# BSPDSpring24.net
KiCad netlist of a schematic drawn in Altium Designer
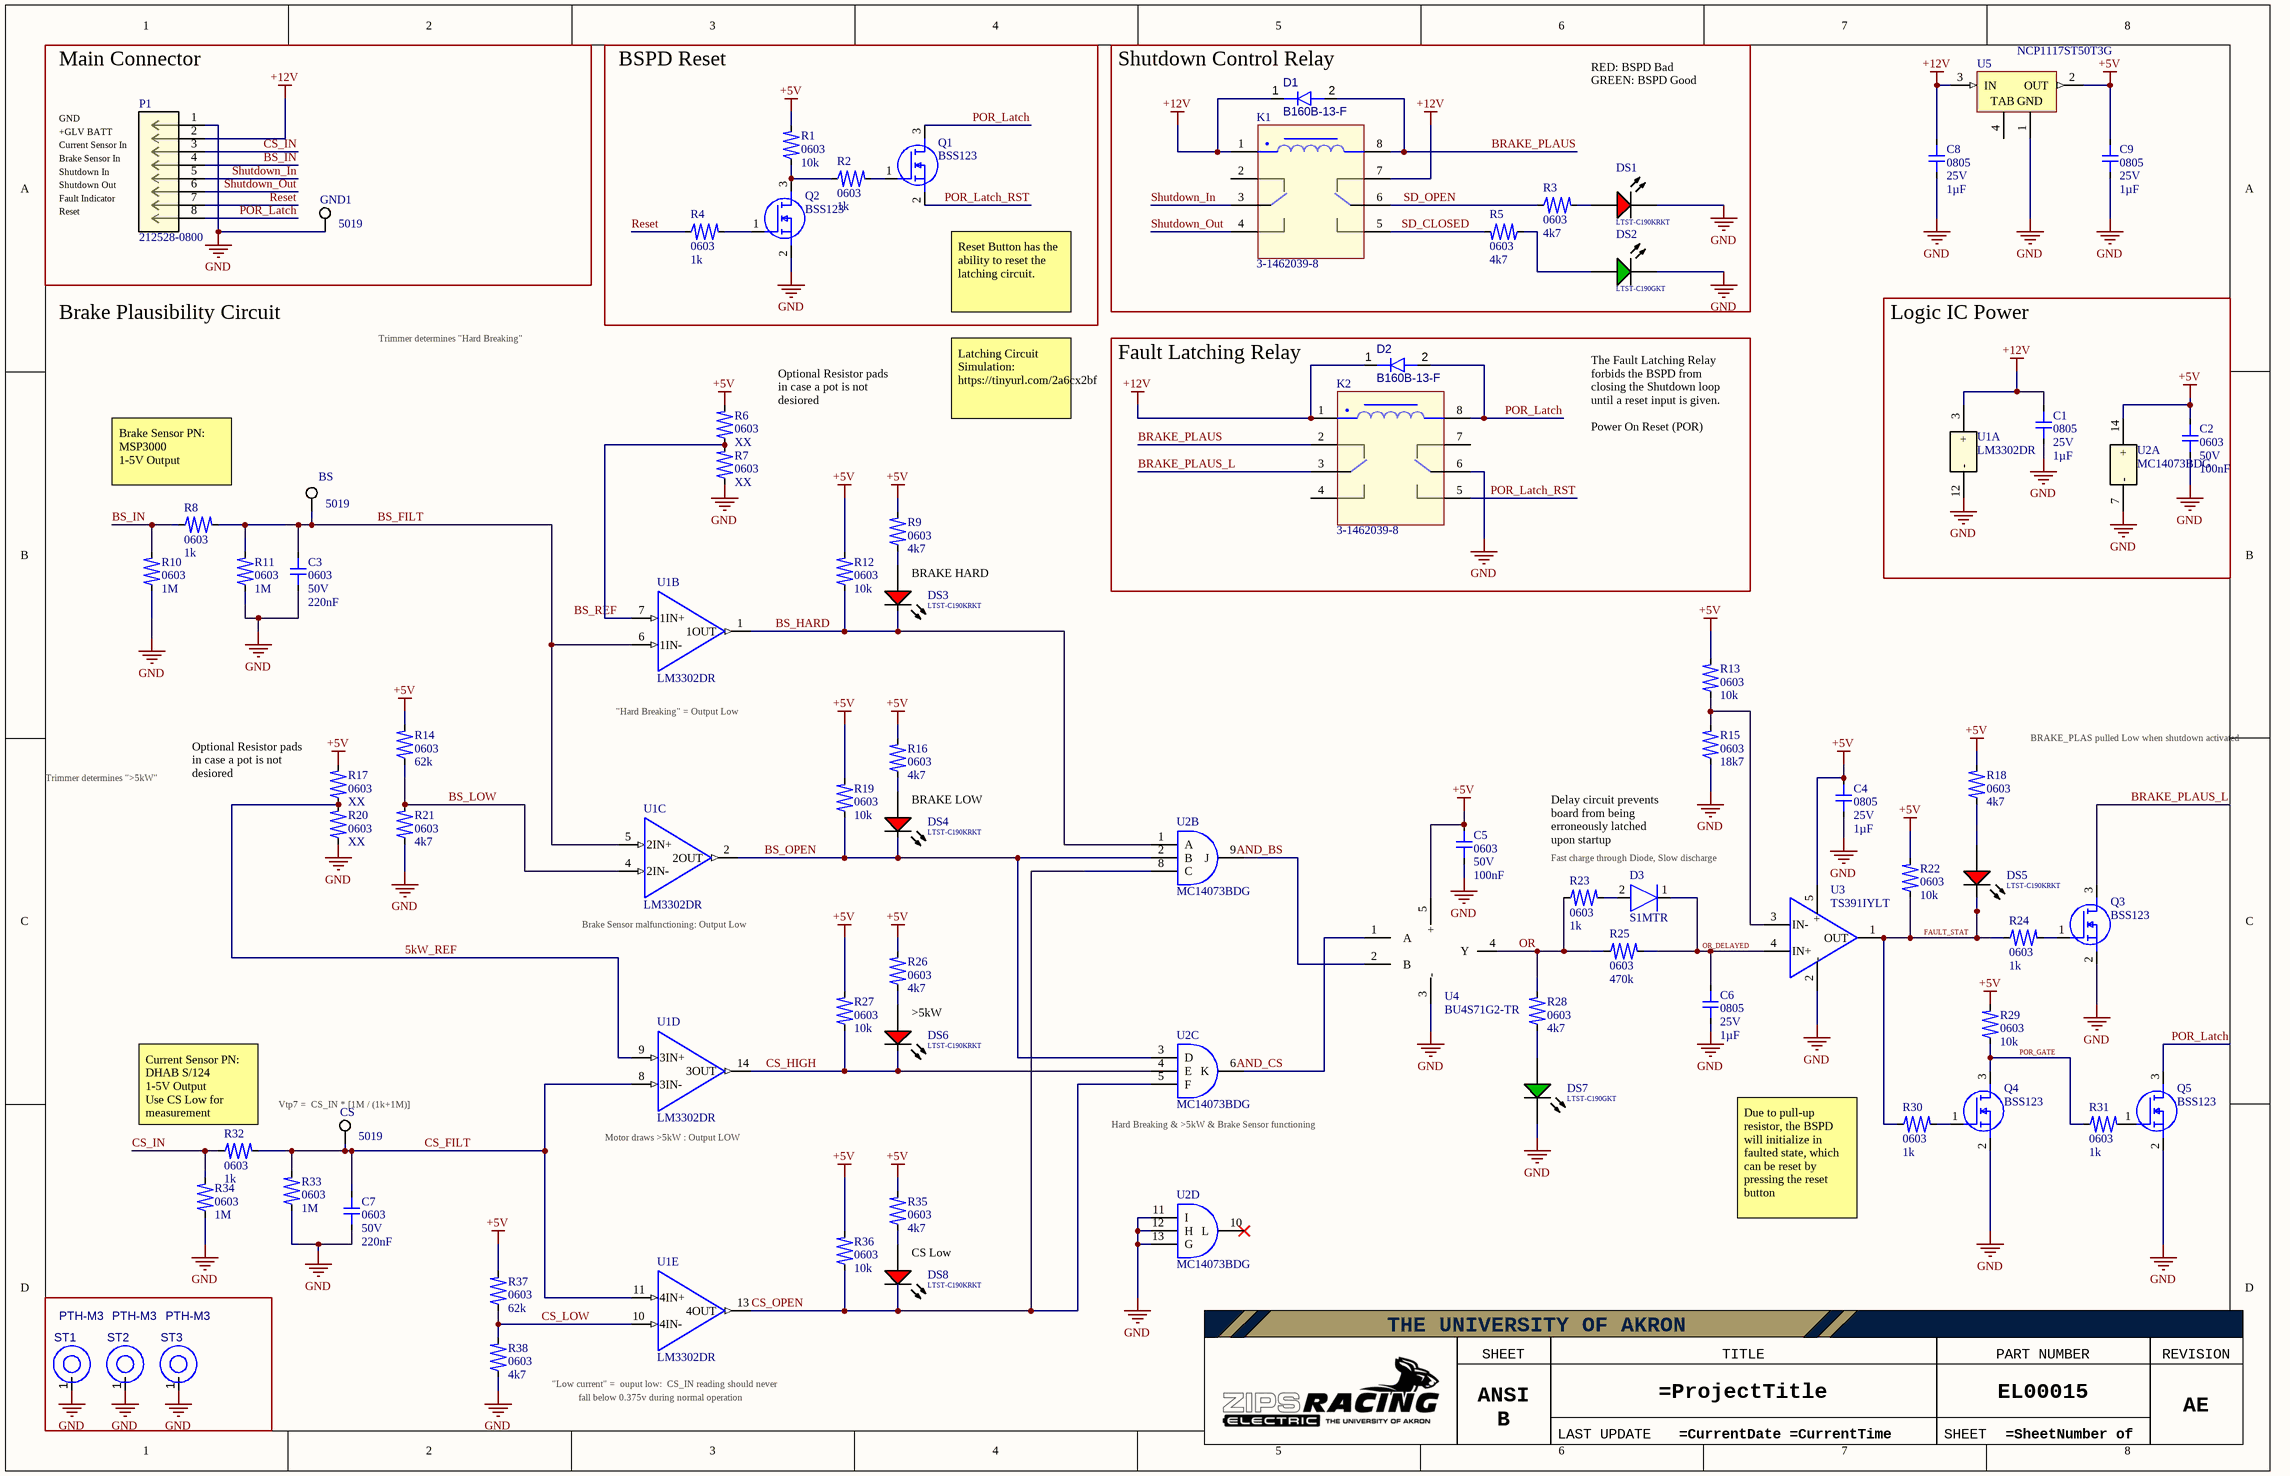
[diagram p0: BSPDSpring24.SchDoc]

(export (version "E")
  (design (tool "Eeschema 10.0.6"))
  (components
    (comp (ref "BS")
      (value "5019")
      (footprint "KSTN-5019_V")
      (description "Interconnection Device")
      (libsource (lib "Zips Racing Electric") (part "TESTPOINT_WHITE"))
    )
    (comp (ref "C1")
      (value "1µF")
      (footprint "0805")
      (description "Capacitor, 0805")
      (fields (field (name "VOLTAGE") "25V") (field (name "Comment") "Capacitor 1uF 0805 25V"))
      (libsource (lib "Zips Racing Electric") (part "CAP-0603"))
    )
    (comp (ref "C2")
      (value "100nF")
      (footprint "0603")
      (description "Capacitor, 0603, 5%")
      (fields (field (name "VOLTAGE") "50V") (field (name "Comment") "Capacitor 100nF 0603 5%"))
      (libsource (lib "Zips Racing Electric") (part "CAP-0603"))
    )
    (comp (ref "C3")
      (value "220nF")
      (footprint "0603")
      (description "Capacitor, 0603, 5%")
      (fields (field (name "VOLTAGE") "50V") (field (name "Comment") "Capacitor 220nF 0603 5%"))
      (libsource (lib "Zips Racing Electric") (part "CAP-0603"))
    )
    (comp (ref "C4")
      (value "1µF")
      (footprint "0805")
      (description "Capacitor, 0805")
      (fields (field (name "VOLTAGE") "25V") (field (name "Comment") "Capacitor 1uF 0805 25V"))
      (libsource (lib "Zips Racing Electric") (part "CAP-0603"))
    )
    (comp (ref "C5")
      (value "100nF")
      (footprint "0603")
      (description "Capacitor, 0603, 5%")
      (fields (field (name "VOLTAGE") "50V") (field (name "Comment") "Capacitor 100nF 0603 5%"))
      (libsource (lib "Zips Racing Electric") (part "CAP-0603"))
    )
    (comp (ref "C6")
      (value "1µF")
      (footprint "0805")
      (description "Capacitor, 0805")
      (fields (field (name "VOLTAGE") "25V") (field (name "Comment") "Capacitor 1uF 0805 25V"))
      (libsource (lib "Zips Racing Electric") (part "CAP-0603"))
    )
    (comp (ref "C7")
      (value "220nF")
      (footprint "0603")
      (description "Capacitor, 0603, 5%")
      (fields (field (name "VOLTAGE") "50V") (field (name "Comment") "Capacitor 220nF 0603 5%"))
      (libsource (lib "Zips Racing Electric") (part "CAP-0603"))
    )
    (comp (ref "C8")
      (value "1µF")
      (footprint "0805")
      (description "Capacitor, 0805")
      (fields (field (name "VOLTAGE") "25V") (field (name "Comment") "Capacitor 1uF 0805 25V"))
      (libsource (lib "Zips Racing Electric") (part "CAP-0603"))
    )
    (comp (ref "C9")
      (value "1µF")
      (footprint "0805")
      (description "Capacitor, 0805")
      (fields (field (name "VOLTAGE") "25V") (field (name "Comment") "Capacitor 1uF 0805 25V"))
      (libsource (lib "Zips Racing Electric") (part "CAP-0603"))
    )
    (comp (ref "CS")
      (value "5019")
      (footprint "KSTN-5019_V")
      (description "Interconnection Device")
      (libsource (lib "Zips Racing Electric") (part "TESTPOINT_WHITE"))
    )
    (comp (ref "D1")
      (value "B160B-13-F")
      (footprint "FP-SMB-MFG")
      (description "Rectifier Diode, Schottky, 1 Phase, 1 Element, 1A, 60V V(RRM), Silicon")
      (libsource (lib "Zips Racing Electric") (part "DIODE-2"))
    )
    (comp (ref "D2")
      (value "B160B-13-F")
      (footprint "FP-SMB-MFG")
      (description "Rectifier Diode, Schottky, 1 Phase, 1 Element, 1A, 60V V(RRM), Silicon")
      (libsource (lib "Zips Racing Electric") (part "DIODE-2"))
    )
    (comp (ref "D3")
      (value "S1MTR")
      (footprint "SMA_SDS")
      (description "Diode Standard 1000 V 1A Surface Mount SMA (DO-214AC)")
      (fields
        (field (name "COPYRIGHT") "Copyright (C) 2021 Ultra Librarian. All rights reserved.")
        (field (name "SOURCE") "Zips_Racing_Electric.SchLib")
      )
      (libsource (lib "Zips Racing Electric") (part "B160B-13-F"))
    )
    (comp (ref "DS1")
      (value "LTST-C190KRKT")
      (footprint "LTST-C191KRKT_V")
      (description "LED Uni-Color Red, 62.5 mW, 25 mA, -30 to 85 degC, 2-Pin SMD, RoHS, Tape and Reel")
      (fields (field (name "POWER") "75mW") (field (name "MANUFACTURER") "Lite-On"))
      (libsource (lib "Zips Racing Electric") (part "LED-RED-AK-2"))
    )
    (comp (ref "DS2")
      (value "LTST-C190GKT")
      (footprint "LTST-C190GKT_V")
      (description "LED Uni-Color Green, 100 mW, 30 mA, -55 to 85 degC, 2-Pin SMD, RoHS, Tape and Reel")
      (fields (field (name "POWER") "100mW") (field (name "MANUFACTURER") "Lite-On"))
      (libsource (lib "Zips Racing Electric") (part "LED-GREEN-AK-2"))
    )
    (comp (ref "DS3")
      (value "LTST-C190KRKT")
      (footprint "LTST-C191KRKT_V")
      (description "LED Uni-Color Red, 62.5 mW, 25 mA, -30 to 85 degC, 2-Pin SMD, RoHS, Tape and Reel")
      (fields (field (name "POWER") "75mW") (field (name "MANUFACTURER") "Lite-On"))
      (libsource (lib "Zips Racing Electric") (part "LED-RED-AK-2"))
    )
    (comp (ref "DS4")
      (value "LTST-C190KRKT")
      (footprint "LTST-C191KRKT_V")
      (description "LED Uni-Color Red, 62.5 mW, 25 mA, -30 to 85 degC, 2-Pin SMD, RoHS, Tape and Reel")
      (fields (field (name "POWER") "75mW") (field (name "MANUFACTURER") "Lite-On"))
      (libsource (lib "Zips Racing Electric") (part "LED-RED-AK-2"))
    )
    (comp (ref "DS5")
      (value "LTST-C190KRKT")
      (footprint "LTST-C191KRKT_V")
      (description "LED Uni-Color Red, 62.5 mW, 25 mA, -30 to 85 degC, 2-Pin SMD, RoHS, Tape and Reel")
      (fields (field (name "POWER") "75mW") (field (name "MANUFACTURER") "Lite-On"))
      (libsource (lib "Zips Racing Electric") (part "LED-RED-AK-2"))
    )
    (comp (ref "DS6")
      (value "LTST-C190KRKT")
      (footprint "LTST-C191KRKT_V")
      (description "LED Uni-Color Red, 62.5 mW, 25 mA, -30 to 85 degC, 2-Pin SMD, RoHS, Tape and Reel")
      (fields (field (name "POWER") "75mW") (field (name "MANUFACTURER") "Lite-On"))
      (libsource (lib "Zips Racing Electric") (part "LED-RED-AK-2"))
    )
    (comp (ref "DS7")
      (value "LTST-C190GKT")
      (footprint "LTST-C190GKT_V")
      (description "LED Uni-Color Green, 100 mW, 30 mA, -55 to 85 degC, 2-Pin SMD, RoHS, Tape and Reel")
      (fields (field (name "POWER") "100mW") (field (name "MANUFACTURER") "Lite-On"))
      (libsource (lib "Zips Racing Electric") (part "LED-GREEN-AK-2"))
    )
    (comp (ref "DS8")
      (value "LTST-C190KRKT")
      (footprint "LTST-C191KRKT_V")
      (description "LED Uni-Color Red, 62.5 mW, 25 mA, -30 to 85 degC, 2-Pin SMD, RoHS, Tape and Reel")
      (fields (field (name "POWER") "75mW") (field (name "MANUFACTURER") "Lite-On"))
      (libsource (lib "Zips Racing Electric") (part "LED-RED-AK-2"))
    )
    (comp (ref "GND1")
      (value "5019")
      (footprint "KSTN-5019_V")
      (description "Interconnection Device")
      (libsource (lib "Zips Racing Electric") (part "TESTPOINT_WHITE"))
    )
    (comp (ref "K1")
      (value "3-1462039-8")
      (footprint "FP-3-1462039-8-MFG")
      (libsource (lib "Zips Racing Electric") (part "f6f6c627aadb73ad41e05903558ffa9"))
    )
    (comp (ref "K2")
      (value "3-1462039-8")
      (footprint "FP-3-1462039-8-MFG")
      (libsource (lib "Zips Racing Electric") (part "f6f6c627aadb73ad41e05903558ffa9"))
    )
    (comp (ref "P1")
      (value "212528-0800")
      (footprint "212528-0800-Footprint-1")
      (description "Connector Power Header 8POS 3mm Solder Right Angle Through Hole Tray")
      (libsource (lib "Zips Racing Electric") (part "212528-0800 (R/A)"))
    )
    (comp (ref "Q1")
      (value "BSS123")
      (footprint "SOT96P237X111-3N")
      (description "MOSFET N-CH 100V 170MA SOT23-3")
      (fields
        (field (name "MOUSER PART NUMBER") "512-BSS123")
        (field (name "SOURCE") "Zips_Racing_Electric.SchLib")
      )
      (libsource (lib "Zips Racing Electric") (part "BSS123"))
    )
    (comp (ref "Q2")
      (value "BSS123")
      (footprint "SOT96P237X111-3N")
      (description "MOSFET N-CH 100V 170MA SOT23-3")
      (fields
        (field (name "MOUSER PART NUMBER") "512-BSS123")
        (field (name "SOURCE") "Zips_Racing_Electric.SchLib")
      )
      (libsource (lib "Zips Racing Electric") (part "BSS123"))
    )
    (comp (ref "Q3")
      (value "BSS123")
      (footprint "SOT96P237X111-3N")
      (description "MOSFET N-CH 100V 170MA SOT23-3")
      (fields
        (field (name "MOUSER PART NUMBER") "512-BSS123")
        (field (name "SOURCE") "Zips_Racing_Electric.SchLib")
      )
      (libsource (lib "Zips Racing Electric") (part "BSS123"))
    )
    (comp (ref "Q4")
      (value "BSS123")
      (footprint "SOT96P237X111-3N")
      (description "MOSFET N-CH 100V 170MA SOT23-3")
      (fields
        (field (name "MOUSER PART NUMBER") "512-BSS123")
        (field (name "SOURCE") "Zips_Racing_Electric.SchLib")
      )
      (libsource (lib "Zips Racing Electric") (part "BSS123"))
    )
    (comp (ref "Q5")
      (value "BSS123")
      (footprint "SOT96P237X111-3N")
      (description "MOSFET N-CH 100V 170MA SOT23-3")
      (fields
        (field (name "MOUSER PART NUMBER") "512-BSS123")
        (field (name "SOURCE") "Zips_Racing_Electric.SchLib")
      )
      (libsource (lib "Zips Racing Electric") (part "BSS123"))
    )
    (comp (ref "R1")
      (value "10k")
      (footprint "0603")
      (description "Resistor, 0603, 10k")
      (fields (field (name "TOLERANCE") "1%") (field (name "POWER") "100mW"))
      (libsource (lib "Zips Racing Electric") (part "RES-0603"))
    )
    (comp (ref "R2")
      (value "1k")
      (footprint "0603")
      (description "Resistor, 0603, 1k")
      (fields (field (name "POWER") "100mW") (field (name "TOLERANCE") "1%"))
      (libsource (lib "Zips Racing Electric") (part "RES-0603"))
    )
    (comp (ref "R3")
      (value "4k7")
      (footprint "0603")
      (description "Resistor, 0603, 1%, 1/10W")
      (fields (field (name "TOLERANCE") "1%") (field (name "POWER") "100mW"))
      (libsource (lib "Zips Racing Electric") (part "RES-0603"))
    )
    (comp (ref "R4")
      (value "1k")
      (footprint "0603")
      (description "Resistor, 0603, 1k")
      (fields (field (name "POWER") "100mW") (field (name "TOLERANCE") "1%"))
      (libsource (lib "Zips Racing Electric") (part "RES-0603"))
    )
    (comp (ref "R5")
      (value "4k7")
      (footprint "0603")
      (description "Resistor, 0603, 1%, 1/10W")
      (fields (field (name "TOLERANCE") "1%") (field (name "POWER") "100mW"))
      (libsource (lib "Zips Racing Electric") (part "RES-0603"))
    )
    (comp (ref "R6")
      (value "XX")
      (footprint "0603")
      (description "Resistor, 0603, XX")
      (fields (field (name "POWER") "100mW") (field (name "TOLERANCE") "1%"))
      (libsource (lib "Zips Racing Electric") (part "RES-0603"))
    )
    (comp (ref "R7")
      (value "XX")
      (footprint "0603")
      (description "Resistor, 0603, XX")
      (fields (field (name "POWER") "100mW") (field (name "TOLERANCE") "1%"))
      (libsource (lib "Zips Racing Electric") (part "RES-0603"))
    )
    (comp (ref "R8")
      (value "1k")
      (footprint "0603")
      (description "Resistor, 0603, 1k")
      (fields (field (name "POWER") "100mW") (field (name "TOLERANCE") "1%"))
      (libsource (lib "Zips Racing Electric") (part "RES-0603"))
    )
    (comp (ref "R9")
      (value "4k7")
      (footprint "0603")
      (description "Resistor, 0603, 1%, 1/10W")
      (fields (field (name "TOLERANCE") "1%") (field (name "POWER") "100mW"))
      (libsource (lib "Zips Racing Electric") (part "RES-0603"))
    )
    (comp (ref "R10")
      (value "1M")
      (footprint "0603")
      (description "Resistor, 0603, 1%, 1/10W")
      (fields (field (name "TOLERANCE") "1%") (field (name "POWER") "100mW"))
      (libsource (lib "Zips Racing Electric") (part "RES-0603"))
    )
    (comp (ref "R11")
      (value "1M")
      (footprint "0603")
      (description "Resistor, 0603, 1%, 1/10W")
      (fields (field (name "TOLERANCE") "1%") (field (name "POWER") "100mW"))
      (libsource (lib "Zips Racing Electric") (part "RES-0603"))
    )
    (comp (ref "R12")
      (value "10k")
      (footprint "0603")
      (description "Resistor, 0603, 10k")
      (fields (field (name "TOLERANCE") "1%") (field (name "POWER") "100mW"))
      (libsource (lib "Zips Racing Electric") (part "RES-0603"))
    )
    (comp (ref "R13")
      (value "10k")
      (footprint "0603")
      (description "Resistor, 0603, 10k")
      (fields (field (name "TOLERANCE") "1%") (field (name "POWER") "100mW"))
      (libsource (lib "Zips Racing Electric") (part "RES-0603"))
    )
    (comp (ref "R14")
      (value "62k")
      (footprint "0603")
      (description "Resistor, 0603, 62k")
      (fields (field (name "POWER") "100mW") (field (name "TOLERANCE") "1%"))
      (libsource (lib "Zips Racing Electric") (part "RES-0603"))
    )
    (comp (ref "R15")
      (value "18k7")
      (footprint "0603")
      (description "Resistor, 0603, 10k")
      (fields (field (name "TOLERANCE") "1%") (field (name "POWER") "100mW"))
      (libsource (lib "Zips Racing Electric") (part "RES-0603"))
    )
    (comp (ref "R16")
      (value "4k7")
      (footprint "0603")
      (description "Resistor, 0603, 1%, 1/10W")
      (fields (field (name "TOLERANCE") "1%") (field (name "POWER") "100mW"))
      (libsource (lib "Zips Racing Electric") (part "RES-0603"))
    )
    (comp (ref "R17")
      (value "XX")
      (footprint "0603")
      (description "Resistor, 0603, XX")
      (fields (field (name "POWER") "100mW") (field (name "TOLERANCE") "1%"))
      (libsource (lib "Zips Racing Electric") (part "RES-0603"))
    )
    (comp (ref "R18")
      (value "4k7")
      (footprint "0603")
      (description "Resistor, 0603, 1%, 1/10W")
      (fields (field (name "TOLERANCE") "1%") (field (name "POWER") "100mW"))
      (libsource (lib "Zips Racing Electric") (part "RES-0603"))
    )
    (comp (ref "R19")
      (value "10k")
      (footprint "0603")
      (description "Resistor, 0603, 10k")
      (fields (field (name "TOLERANCE") "1%") (field (name "POWER") "100mW"))
      (libsource (lib "Zips Racing Electric") (part "RES-0603"))
    )
    (comp (ref "R20")
      (value "XX")
      (footprint "0603")
      (description "Resistor, 0603, XX")
      (fields (field (name "POWER") "100mW") (field (name "TOLERANCE") "1%"))
      (libsource (lib "Zips Racing Electric") (part "RES-0603"))
    )
    (comp (ref "R21")
      (value "4k7")
      (footprint "0603")
      (description "Resistor, 0603, 1%, 1/10W")
      (fields (field (name "TOLERANCE") "1%") (field (name "POWER") "100mW"))
      (libsource (lib "Zips Racing Electric") (part "RES-0603"))
    )
    (comp (ref "R22")
      (value "10k")
      (footprint "0603")
      (description "Resistor, 0603, 10k")
      (fields (field (name "TOLERANCE") "1%") (field (name "POWER") "100mW"))
      (libsource (lib "Zips Racing Electric") (part "RES-0603"))
    )
    (comp (ref "R23")
      (value "1k")
      (footprint "0603")
      (description "Resistor, 0603, 1k")
      (fields (field (name "POWER") "100mW") (field (name "TOLERANCE") "1%"))
      (libsource (lib "Zips Racing Electric") (part "RES-0603"))
    )
    (comp (ref "R24")
      (value "1k")
      (footprint "0603")
      (description "Resistor, 0603, 1k")
      (fields (field (name "POWER") "100mW") (field (name "TOLERANCE") "1%"))
      (libsource (lib "Zips Racing Electric") (part "RES-0603"))
    )
    (comp (ref "R25")
      (value "470k")
      (footprint "0603")
      (description "Resistor, 0603, 1%, 1/10W")
      (fields (field (name "POWER") "100mW") (field (name "TOLERANCE") "1%"))
      (libsource (lib "Zips Racing Electric") (part "RES-0603"))
    )
    (comp (ref "R26")
      (value "4k7")
      (footprint "0603")
      (description "Resistor, 0603, 1%, 1/10W")
      (fields (field (name "TOLERANCE") "1%") (field (name "POWER") "100mW"))
      (libsource (lib "Zips Racing Electric") (part "RES-0603"))
    )
    (comp (ref "R27")
      (value "10k")
      (footprint "0603")
      (description "Resistor, 0603, 10k")
      (fields (field (name "TOLERANCE") "1%") (field (name "POWER") "100mW"))
      (libsource (lib "Zips Racing Electric") (part "RES-0603"))
    )
    (comp (ref "R28")
      (value "4k7")
      (footprint "0603")
      (description "Resistor, 0603, 1%, 1/10W")
      (fields (field (name "TOLERANCE") "1%") (field (name "POWER") "100mW"))
      (libsource (lib "Zips Racing Electric") (part "RES-0603"))
    )
    (comp (ref "R29")
      (value "10k")
      (footprint "0603")
      (description "Resistor, 0603, 10k")
      (fields (field (name "TOLERANCE") "1%") (field (name "POWER") "100mW"))
      (libsource (lib "Zips Racing Electric") (part "RES-0603"))
    )
    (comp (ref "R30")
      (value "1k")
      (footprint "0603")
      (description "Resistor, 0603, 1k")
      (fields (field (name "POWER") "100mW") (field (name "TOLERANCE") "1%"))
      (libsource (lib "Zips Racing Electric") (part "RES-0603"))
    )
    (comp (ref "R31")
      (value "1k")
      (footprint "0603")
      (description "Resistor, 0603, 1k")
      (fields (field (name "POWER") "100mW") (field (name "TOLERANCE") "1%"))
      (libsource (lib "Zips Racing Electric") (part "RES-0603"))
    )
    (comp (ref "R32")
      (value "1k")
      (footprint "0603")
      (description "Resistor, 0603, 1k")
      (fields (field (name "POWER") "100mW") (field (name "TOLERANCE") "1%"))
      (libsource (lib "Zips Racing Electric") (part "RES-0603"))
    )
    (comp (ref "R33")
      (value "1M")
      (footprint "0603")
      (description "Resistor, 0603, 1%, 1/10W")
      (fields (field (name "TOLERANCE") "1%") (field (name "POWER") "100mW"))
      (libsource (lib "Zips Racing Electric") (part "RES-0603"))
    )
    (comp (ref "R34")
      (value "1M")
      (footprint "0603")
      (description "Resistor, 0603, 1%, 1/10W")
      (fields (field (name "TOLERANCE") "1%") (field (name "POWER") "100mW"))
      (libsource (lib "Zips Racing Electric") (part "RES-0603"))
    )
    (comp (ref "R35")
      (value "4k7")
      (footprint "0603")
      (description "Resistor, 0603, 1%, 1/10W")
      (fields (field (name "TOLERANCE") "1%") (field (name "POWER") "100mW"))
      (libsource (lib "Zips Racing Electric") (part "RES-0603"))
    )
    (comp (ref "R36")
      (value "10k")
      (footprint "0603")
      (description "Resistor, 0603, 10k")
      (fields (field (name "TOLERANCE") "1%") (field (name "POWER") "100mW"))
      (libsource (lib "Zips Racing Electric") (part "RES-0603"))
    )
    (comp (ref "R37")
      (value "62k")
      (footprint "0603")
      (description "Resistor, 0603, 62k")
      (fields (field (name "POWER") "100mW") (field (name "TOLERANCE") "1%"))
      (libsource (lib "Zips Racing Electric") (part "RES-0603"))
    )
    (comp (ref "R38")
      (value "4k7")
      (footprint "0603")
      (description "Resistor, 0603, 1%, 1/10W")
      (fields (field (name "TOLERANCE") "1%") (field (name "POWER") "100mW"))
      (libsource (lib "Zips Racing Electric") (part "RES-0603"))
    )
    (comp (ref "ST1")
      (value "PTH-M3")
      (footprint "PTH-M2D5X5")
      (description "M3 Plated Thru-Hole  (3.2mm), 7mm pad, 10 mm keep out zone")
      (libsource (lib "Zips Racing Electric") (part "CMP-00028-00000-1"))
    )
    (comp (ref "ST2")
      (value "PTH-M3")
      (footprint "PTH-M2D5X5")
      (description "M3 Plated Thru-Hole  (3.2mm), 7mm pad, 10 mm keep out zone")
      (libsource (lib "Zips Racing Electric") (part "CMP-00028-00000-1"))
    )
    (comp (ref "ST3")
      (value "PTH-M3")
      (footprint "PTH-M2D5X5")
      (description "M3 Plated Thru-Hole  (3.2mm), 7mm pad, 10 mm keep out zone")
      (libsource (lib "Zips Racing Electric") (part "CMP-00028-00000-1"))
    )
    (comp (ref "U1")
      (value "LM3302DR")
      (footprint "SOIC127P600X175-14N")
      (description "Quad, General Purpose Differential Comparator")
      (fields (field (name "MF") "Texas Instruments"))
      (libsource (lib "Zips Racing Electric") (part "LM3302DR_1"))
    )
    (comp (ref "U2")
      (value "MC14073BDG")
      (footprint "MC14073BDG-Footprint-1")
      (description "MC14073BDG; Triple 3-Input AND Logic Gate; 3 - 18 V; 14-Pin SOIC")
      (libsource (lib "Zips Racing Electric") (part "MC14073BDG-Symbol-1"))
    )
    (comp (ref "U3")
      (value "TS391IYLT")
      (footprint "SOT23-5_STM")
      (description "Comparator General Purpose CMOS, DTL, ECL, Open-Collector, TTL SOT-23-5")
      (fields
        (field (name "COPYRIGHT") "Copyright (C) 2021 Ultra Librarian. All rights reserved.")
        (field (name "SOURCE") "Zips_Racing_Electric.SchLib")
      )
      (libsource (lib "Zips Racing Electric") (part "TS391IYLT"))
    )
    (comp (ref "U4")
      (value "BU4S71G2-TR")
      (footprint "SSOP5_ROM-L")
      (description "IC GATE OR 1CH 2-INP 5SSOP")
      (fields
        (field (name "COPYRIGHT") "Copyright (C) 2018 Accelerated Designs. All rights reserved")
        (field (name "SOURCE") "Zips_Racing_Electric.SchLib")
      )
      (libsource (lib "Zips Racing Electric") (part "BU4S71G2-TR"))
    )
    (comp (ref "U5")
      (value "NCP1117ST50T3G")
      (footprint "ONSC-SOT-223-4-318H-01_A_V")
      (fields (field (name "MANUFACTURER") "ON Semiconductor"))
      (libsource (lib "Zips Racing Electric") (part "ONSC-NCP1117ST-TO-223-4"))
    )
  )
  (nets
    (net (code "1") (name "+5V") (class "Default")
      (node (ref "C2") (pin "2") (pinfunction "2_2") (pintype "passive"))
      (node (ref "C4") (pin "2") (pinfunction "2_2") (pintype "passive"))
      (node (ref "C5") (pin "2") (pinfunction "2_2") (pintype "passive"))
      (node (ref "C9") (pin "2") (pinfunction "2_2") (pintype "passive"))
      (node (ref "R1") (pin "2") (pinfunction "2_2") (pintype "passive"))
      (node (ref "R12") (pin "2") (pinfunction "2_2") (pintype "passive"))
      (node (ref "R13") (pin "2") (pinfunction "2_2") (pintype "passive"))
      (node (ref "R14") (pin "2") (pinfunction "2_2") (pintype "passive"))
      (node (ref "R16") (pin "2") (pinfunction "2_2") (pintype "passive"))
      (node (ref "R17") (pin "2") (pinfunction "2_2") (pintype "passive"))
      (node (ref "R18") (pin "2") (pinfunction "2_2") (pintype "passive"))
      (node (ref "R19") (pin "2") (pinfunction "2_2") (pintype "passive"))
      (node (ref "R22") (pin "2") (pinfunction "2_2") (pintype "passive"))
      (node (ref "R26") (pin "2") (pinfunction "2_2") (pintype "passive"))
      (node (ref "R27") (pin "2") (pinfunction "2_2") (pintype "passive"))
      (node (ref "R29") (pin "2") (pinfunction "2_2") (pintype "passive"))
      (node (ref "R35") (pin "2") (pinfunction "2_2") (pintype "passive"))
      (node (ref "R36") (pin "2") (pinfunction "2_2") (pintype "passive"))
      (node (ref "R37") (pin "2") (pinfunction "2_2") (pintype "passive"))
      (node (ref "R6") (pin "2") (pinfunction "2_2") (pintype "passive"))
      (node (ref "R9") (pin "2") (pinfunction "2_2") (pintype "passive"))
      (node (ref "U2") (pin "14") (pinfunction "+_14") (pintype "power_in"))
      (node (ref "U3") (pin "5") (pinfunction "+_5") (pintype "passive"))
      (node (ref "U4") (pin "5") (pinfunction "+_5") (pintype "power_in"))
      (node (ref "U5") (pin "2") (pinfunction "OUT_2") (pintype "output"))
    )
    (net (code "2") (name "+12V") (class "Default")
      (node (ref "C1") (pin "2") (pinfunction "2_2") (pintype "passive"))
      (node (ref "C8") (pin "2") (pinfunction "2_2") (pintype "passive"))
      (node (ref "D1") (pin "1") (pinfunction "K_1") (pintype "passive"))
      (node (ref "D2") (pin "1") (pinfunction "K_1") (pintype "passive"))
      (node (ref "K1") (pin "1") (pinfunction "1_1") (pintype "passive"))
      (node (ref "K1") (pin "7") (pinfunction "7_7") (pintype "passive"))
      (node (ref "K2") (pin "1") (pinfunction "1_1") (pintype "passive"))
      (node (ref "P1") (pin "2") (pinfunction "2_2") (pintype "passive"))
      (node (ref "U1") (pin "3") (pinfunction "+_3") (pintype "power_in"))
      (node (ref "U5") (pin "3") (pinfunction "IN_3") (pintype "input"))
    )
    (net (code "3") (name "/5kW_REF") (class "Default")
      (node (ref "R17") (pin "1") (pinfunction "1_1") (pintype "passive"))
      (node (ref "R20") (pin "2") (pinfunction "2_2") (pintype "passive"))
      (node (ref "U1") (pin "9") (pinfunction "3IN+_9") (pintype "input"))
    )
    (net (code "4") (name "/AND_BS") (class "Default")
      (node (ref "U2") (pin "9") (pinfunction "J_9") (pintype "passive"))
      (node (ref "U4") (pin "2") (pinfunction "B_2") (pintype "passive"))
    )
    (net (code "5") (name "/AND_CS") (class "Default")
      (node (ref "U2") (pin "6") (pinfunction "K_6") (pintype "passive"))
      (node (ref "U4") (pin "1") (pinfunction "A_1") (pintype "passive"))
    )
    (net (code "6") (name "/BRAKE_PLAUS") (class "Default")
      (node (ref "D1") (pin "2") (pinfunction "A_2") (pintype "passive"))
      (node (ref "K1") (pin "8") (pinfunction "8_8") (pintype "passive"))
      (node (ref "K2") (pin "2") (pinfunction "2_2") (pintype "passive"))
    )
    (net (code "7") (name "/BRAKE_PLAUS_L") (class "Default")
      (node (ref "K2") (pin "3") (pinfunction "3_3") (pintype "passive"))
      (node (ref "Q3") (pin "3") (pinfunction "D_3") (pintype "passive"))
    )
    (net (code "8") (name "/BS_FILT") (class "Default")
      (node (ref "BS") (pin "1") (pinfunction "1_1") (pintype "passive"))
      (node (ref "C3") (pin "2") (pinfunction "2_2") (pintype "passive"))
      (node (ref "R11") (pin "2") (pinfunction "2_2") (pintype "passive"))
      (node (ref "R8") (pin "2") (pinfunction "2_2") (pintype "passive"))
      (node (ref "U1") (pin "5") (pinfunction "2IN+_5") (pintype "input"))
      (node (ref "U1") (pin "6") (pinfunction "1IN-_6") (pintype "input"))
    )
    (net (code "9") (name "/BS_HARD") (class "Default")
      (node (ref "DS3") (pin "2") (pinfunction "K_2") (pintype "passive"))
      (node (ref "R12") (pin "1") (pinfunction "1_1") (pintype "passive"))
      (node (ref "U1") (pin "1") (pinfunction "1OUT_1") (pintype "output"))
      (node (ref "U2") (pin "1") (pinfunction "A_1") (pintype "passive"))
    )
    (net (code "10") (name "/BS_IN") (class "Default")
      (node (ref "P1") (pin "4") (pinfunction "4_4") (pintype "passive"))
      (node (ref "R10") (pin "2") (pinfunction "2_2") (pintype "passive"))
      (node (ref "R8") (pin "1") (pinfunction "1_1") (pintype "passive"))
    )
    (net (code "11") (name "/BS_LOW") (class "Default")
      (node (ref "R14") (pin "1") (pinfunction "1_1") (pintype "passive"))
      (node (ref "R21") (pin "2") (pinfunction "2_2") (pintype "passive"))
      (node (ref "U1") (pin "4") (pinfunction "2IN-_4") (pintype "input"))
    )
    (net (code "12") (name "/BS_OPEN") (class "Default")
      (node (ref "DS4") (pin "2") (pinfunction "K_2") (pintype "passive"))
      (node (ref "R19") (pin "1") (pinfunction "1_1") (pintype "passive"))
      (node (ref "U1") (pin "2") (pinfunction "2OUT_2") (pintype "output"))
      (node (ref "U2") (pin "2") (pinfunction "B_2") (pintype "passive"))
      (node (ref "U2") (pin "3") (pinfunction "D_3") (pintype "passive"))
    )
    (net (code "13") (name "/BS_REF") (class "Default")
      (node (ref "R6") (pin "1") (pinfunction "1_1") (pintype "passive"))
      (node (ref "R7") (pin "2") (pinfunction "2_2") (pintype "passive"))
      (node (ref "U1") (pin "7") (pinfunction "1IN+_7") (pintype "input"))
    )
    (net (code "14") (name "/CS_FILT") (class "Default")
      (node (ref "C7") (pin "2") (pinfunction "2_2") (pintype "passive"))
      (node (ref "CS") (pin "1") (pinfunction "1_1") (pintype "passive"))
      (node (ref "R32") (pin "2") (pinfunction "2_2") (pintype "passive"))
      (node (ref "R33") (pin "2") (pinfunction "2_2") (pintype "passive"))
      (node (ref "U1") (pin "11") (pinfunction "4IN+_11") (pintype "input"))
      (node (ref "U1") (pin "8") (pinfunction "3IN-_8") (pintype "input"))
    )
    (net (code "15") (name "/CS_HIGH") (class "Default")
      (node (ref "DS6") (pin "2") (pinfunction "K_2") (pintype "passive"))
      (node (ref "R27") (pin "1") (pinfunction "1_1") (pintype "passive"))
      (node (ref "U1") (pin "14") (pinfunction "3OUT_14") (pintype "output"))
      (node (ref "U2") (pin "4") (pinfunction "E_4") (pintype "passive"))
    )
    (net (code "16") (name "/CS_IN") (class "Default")
      (node (ref "P1") (pin "3") (pinfunction "3_3") (pintype "passive"))
      (node (ref "R32") (pin "1") (pinfunction "1_1") (pintype "passive"))
      (node (ref "R34") (pin "2") (pinfunction "2_2") (pintype "passive"))
    )
    (net (code "17") (name "/CS_LOW") (class "Default")
      (node (ref "R37") (pin "1") (pinfunction "1_1") (pintype "passive"))
      (node (ref "R38") (pin "2") (pinfunction "2_2") (pintype "passive"))
      (node (ref "U1") (pin "10") (pinfunction "4IN-_10") (pintype "input"))
    )
    (net (code "18") (name "/CS_OPEN") (class "Default")
      (node (ref "DS8") (pin "2") (pinfunction "K_2") (pintype "passive"))
      (node (ref "R36") (pin "1") (pinfunction "1_1") (pintype "passive"))
      (node (ref "U1") (pin "13") (pinfunction "4OUT_13") (pintype "output"))
      (node (ref "U2") (pin "5") (pinfunction "F_5") (pintype "passive"))
      (node (ref "U2") (pin "8") (pinfunction "C_8") (pintype "passive"))
    )
    (net (code "19") (name "/FAULT_STAT") (class "Default")
      (node (ref "DS5") (pin "2") (pinfunction "K_2") (pintype "passive"))
      (node (ref "R22") (pin "1") (pinfunction "1_1") (pintype "passive"))
      (node (ref "R24") (pin "1") (pinfunction "1_1") (pintype "passive"))
      (node (ref "R30") (pin "1") (pinfunction "1_1") (pintype "passive"))
      (node (ref "U3") (pin "1") (pinfunction "OUT_1") (pintype "passive"))
    )
    (net (code "20") (name "/OR") (class "Default")
      (node (ref "R23") (pin "1") (pinfunction "1_1") (pintype "passive"))
      (node (ref "R25") (pin "1") (pinfunction "1_1") (pintype "passive"))
      (node (ref "R28") (pin "2") (pinfunction "2_2") (pintype "passive"))
      (node (ref "U4") (pin "4") (pinfunction "Y_4") (pintype "passive"))
    )
    (net (code "21") (name "/OR_DELAYED") (class "Default")
      (node (ref "C6") (pin "2") (pinfunction "2_2") (pintype "passive"))
      (node (ref "D3") (pin "1") (pinfunction "K_1") (pintype "passive"))
      (node (ref "R25") (pin "2") (pinfunction "2_2") (pintype "passive"))
      (node (ref "U3") (pin "4") (pinfunction "IN+_4") (pintype "passive"))
    )
    (net (code "22") (name "/POR_GATE") (class "Default")
      (node (ref "Q4") (pin "3") (pinfunction "D_3") (pintype "passive"))
      (node (ref "R29") (pin "1") (pinfunction "1_1") (pintype "passive"))
      (node (ref "R31") (pin "1") (pinfunction "1_1") (pintype "passive"))
    )
    (net (code "23") (name "/POR_Latch") (class "Default")
      (node (ref "D2") (pin "2") (pinfunction "A_2") (pintype "passive"))
      (node (ref "K2") (pin "8") (pinfunction "8_8") (pintype "passive"))
      (node (ref "P1") (pin "8") (pinfunction "8_8") (pintype "passive"))
      (node (ref "Q1") (pin "3") (pinfunction "D_3") (pintype "passive"))
      (node (ref "Q5") (pin "3") (pinfunction "D_3") (pintype "passive"))
    )
    (net (code "24") (name "/POR_Latch_RST") (class "Default")
      (node (ref "K2") (pin "5") (pinfunction "5_5") (pintype "passive"))
      (node (ref "Q1") (pin "2") (pinfunction "S_2") (pintype "passive"))
    )
    (net (code "25") (name "/Reset") (class "Default")
      (node (ref "P1") (pin "7") (pinfunction "7_7") (pintype "passive"))
      (node (ref "R4") (pin "1") (pinfunction "1_1") (pintype "passive"))
    )
    (net (code "26") (name "/SD_CLOSED") (class "Default")
      (node (ref "K1") (pin "5") (pinfunction "5_5") (pintype "passive"))
      (node (ref "R5") (pin "2") (pinfunction "2_2") (pintype "passive"))
    )
    (net (code "27") (name "/SD_OPEN") (class "Default")
      (node (ref "K1") (pin "6") (pinfunction "6_6") (pintype "passive"))
      (node (ref "R3") (pin "1") (pinfunction "1_1") (pintype "passive"))
    )
    (net (code "28") (name "/Shutdown_In") (class "Default")
      (node (ref "K1") (pin "3") (pinfunction "3_3") (pintype "passive"))
      (node (ref "P1") (pin "5") (pinfunction "5_5") (pintype "passive"))
    )
    (net (code "29") (name "/Shutdown_Out") (class "Default")
      (node (ref "K1") (pin "4") (pinfunction "4_4") (pintype "passive"))
      (node (ref "P1") (pin "6") (pinfunction "6_6") (pintype "passive"))
    )
    (net (code "30") (name "GND") (class "Default")
      (node (ref "C1") (pin "1") (pinfunction "1_1") (pintype "passive"))
      (node (ref "C2") (pin "1") (pinfunction "1_1") (pintype "passive"))
      (node (ref "C3") (pin "1") (pinfunction "1_1") (pintype "passive"))
      (node (ref "C4") (pin "1") (pinfunction "1_1") (pintype "passive"))
      (node (ref "C5") (pin "1") (pinfunction "1_1") (pintype "passive"))
      (node (ref "C6") (pin "1") (pinfunction "1_1") (pintype "passive"))
      (node (ref "C7") (pin "1") (pinfunction "1_1") (pintype "passive"))
      (node (ref "C8") (pin "1") (pinfunction "1_1") (pintype "passive"))
      (node (ref "C9") (pin "1") (pinfunction "1_1") (pintype "passive"))
      (node (ref "DS1") (pin "2") (pinfunction "K_2") (pintype "passive"))
      (node (ref "DS2") (pin "2") (pinfunction "K_2") (pintype "passive"))
      (node (ref "DS7") (pin "2") (pinfunction "K_2") (pintype "passive"))
      (node (ref "GND1") (pin "1") (pinfunction "1_1") (pintype "passive"))
      (node (ref "K2") (pin "6") (pinfunction "6_6") (pintype "passive"))
      (node (ref "P1") (pin "1") (pinfunction "1_1") (pintype "passive"))
      (node (ref "Q2") (pin "2") (pinfunction "S_2") (pintype "passive"))
      (node (ref "Q3") (pin "2") (pinfunction "S_2") (pintype "passive"))
      (node (ref "Q4") (pin "2") (pinfunction "S_2") (pintype "passive"))
      (node (ref "Q5") (pin "2") (pinfunction "S_2") (pintype "passive"))
      (node (ref "R10") (pin "1") (pinfunction "1_1") (pintype "passive"))
      (node (ref "R11") (pin "1") (pinfunction "1_1") (pintype "passive"))
      (node (ref "R15") (pin "1") (pinfunction "1_1") (pintype "passive"))
      (node (ref "R20") (pin "1") (pinfunction "1_1") (pintype "passive"))
      (node (ref "R21") (pin "1") (pinfunction "1_1") (pintype "passive"))
      (node (ref "R33") (pin "1") (pinfunction "1_1") (pintype "passive"))
      (node (ref "R34") (pin "1") (pinfunction "1_1") (pintype "passive"))
      (node (ref "R38") (pin "1") (pinfunction "1_1") (pintype "passive"))
      (node (ref "R7") (pin "1") (pinfunction "1_1") (pintype "passive"))
      (node (ref "ST1") (pin "1") (pinfunction "H1_1") (pintype "passive"))
      (node (ref "ST2") (pin "1") (pinfunction "H1_1") (pintype "passive"))
      (node (ref "ST3") (pin "1") (pinfunction "H1_1") (pintype "passive"))
      (node (ref "U1") (pin "12") (pinfunction "-_12") (pintype "power_in"))
      (node (ref "U2") (pin "11") (pinfunction "I_11") (pintype "passive"))
      (node (ref "U2") (pin "12") (pinfunction "H_12") (pintype "passive"))
      (node (ref "U2") (pin "13") (pinfunction "G_13") (pintype "passive"))
      (node (ref "U2") (pin "7") (pinfunction "-_7") (pintype "power_in"))
      (node (ref "U3") (pin "2") (pinfunction "-_2") (pintype "passive"))
      (node (ref "U4") (pin "3") (pinfunction "-_3") (pintype "passive"))
      (node (ref "U5") (pin "1") (pinfunction "GND_1") (pintype "power_in"))
    )
    (net (code "31") (name "Net-(D3-A)") (class "Default")
      (node (ref "D3") (pin "2") (pinfunction "A_2") (pintype "passive"))
      (node (ref "R23") (pin "2") (pinfunction "2_2") (pintype "passive"))
    )
    (net (code "32") (name "Net-(DS1-A)") (class "Default")
      (node (ref "DS1") (pin "1") (pinfunction "A_1") (pintype "passive"))
      (node (ref "R3") (pin "2") (pinfunction "2_2") (pintype "passive"))
    )
    (net (code "33") (name "Net-(DS2-A)") (class "Default")
      (node (ref "DS2") (pin "1") (pinfunction "A_1") (pintype "passive"))
      (node (ref "R5") (pin "1") (pinfunction "1_1") (pintype "passive"))
    )
    (net (code "34") (name "Net-(DS3-A)") (class "Default")
      (node (ref "DS3") (pin "1") (pinfunction "A_1") (pintype "passive"))
      (node (ref "R9") (pin "1") (pinfunction "1_1") (pintype "passive"))
    )
    (net (code "35") (name "Net-(DS4-A)") (class "Default")
      (node (ref "DS4") (pin "1") (pinfunction "A_1") (pintype "passive"))
      (node (ref "R16") (pin "1") (pinfunction "1_1") (pintype "passive"))
    )
    (net (code "36") (name "Net-(DS5-A)") (class "Default")
      (node (ref "DS5") (pin "1") (pinfunction "A_1") (pintype "passive"))
      (node (ref "R18") (pin "1") (pinfunction "1_1") (pintype "passive"))
    )
    (net (code "37") (name "Net-(DS6-A)") (class "Default")
      (node (ref "DS6") (pin "1") (pinfunction "A_1") (pintype "passive"))
      (node (ref "R26") (pin "1") (pinfunction "1_1") (pintype "passive"))
    )
    (net (code "38") (name "Net-(DS7-A)") (class "Default")
      (node (ref "DS7") (pin "1") (pinfunction "A_1") (pintype "passive"))
      (node (ref "R28") (pin "1") (pinfunction "1_1") (pintype "passive"))
    )
    (net (code "39") (name "Net-(DS8-A)") (class "Default")
      (node (ref "DS8") (pin "1") (pinfunction "A_1") (pintype "passive"))
      (node (ref "R35") (pin "1") (pinfunction "1_1") (pintype "passive"))
    )
    (net (code "40") (name "Net-(Q1-G)") (class "Default")
      (node (ref "Q1") (pin "1") (pinfunction "G_1") (pintype "passive"))
      (node (ref "R2") (pin "2") (pinfunction "2_2") (pintype "passive"))
    )
    (net (code "41") (name "Net-(Q2-D)") (class "Default")
      (node (ref "Q2") (pin "3") (pinfunction "D_3") (pintype "passive"))
      (node (ref "R1") (pin "1") (pinfunction "1_1") (pintype "passive"))
      (node (ref "R2") (pin "1") (pinfunction "1_1") (pintype "passive"))
    )
    (net (code "42") (name "Net-(Q2-G)") (class "Default")
      (node (ref "Q2") (pin "1") (pinfunction "G_1") (pintype "passive"))
      (node (ref "R4") (pin "2") (pinfunction "2_2") (pintype "passive"))
    )
    (net (code "43") (name "Net-(Q3-G)") (class "Default")
      (node (ref "Q3") (pin "1") (pinfunction "G_1") (pintype "passive"))
      (node (ref "R24") (pin "2") (pinfunction "2_2") (pintype "passive"))
    )
    (net (code "44") (name "Net-(Q4-G)") (class "Default")
      (node (ref "Q4") (pin "1") (pinfunction "G_1") (pintype "passive"))
      (node (ref "R30") (pin "2") (pinfunction "2_2") (pintype "passive"))
    )
    (net (code "45") (name "Net-(Q5-G)") (class "Default")
      (node (ref "Q5") (pin "1") (pinfunction "G_1") (pintype "passive"))
      (node (ref "R31") (pin "2") (pinfunction "2_2") (pintype "passive"))
    )
    (net (code "46") (name "Net-(U3-IN-)") (class "Default")
      (node (ref "R13") (pin "1") (pinfunction "1_1") (pintype "passive"))
      (node (ref "R15") (pin "2") (pinfunction "2_2") (pintype "passive"))
      (node (ref "U3") (pin "3") (pinfunction "IN-_3") (pintype "passive"))
    )
    (net (code "47") (name "unconnected-(K1-Pad2)") (class "Default")
      (node (ref "K1") (pin "2") (pinfunction "2_2") (pintype "passive"))
    )
    (net (code "48") (name "unconnected-(K2-Pad4)") (class "Default")
      (node (ref "K2") (pin "4") (pinfunction "4_4") (pintype "passive"))
    )
    (net (code "49") (name "unconnected-(K2-Pad7)") (class "Default")
      (node (ref "K2") (pin "7") (pinfunction "7_7") (pintype "passive"))
    )
    (net (code "50") (name "unconnected-(U2D-L-Pad10)") (class "Default")
      (node (ref "U2") (pin "10") (pinfunction "L_10") (pintype "passive+no_connect"))
    )
    (net (code "51") (name "unconnected-(U5-TAB-Pad4)") (class "Default")
      (node (ref "U5") (pin "4") (pinfunction "TAB_4") (pintype "power_in"))
    )
  )
)
